# Buck_5V.net
KiCad netlist of a schematic drawn in Altium Designer
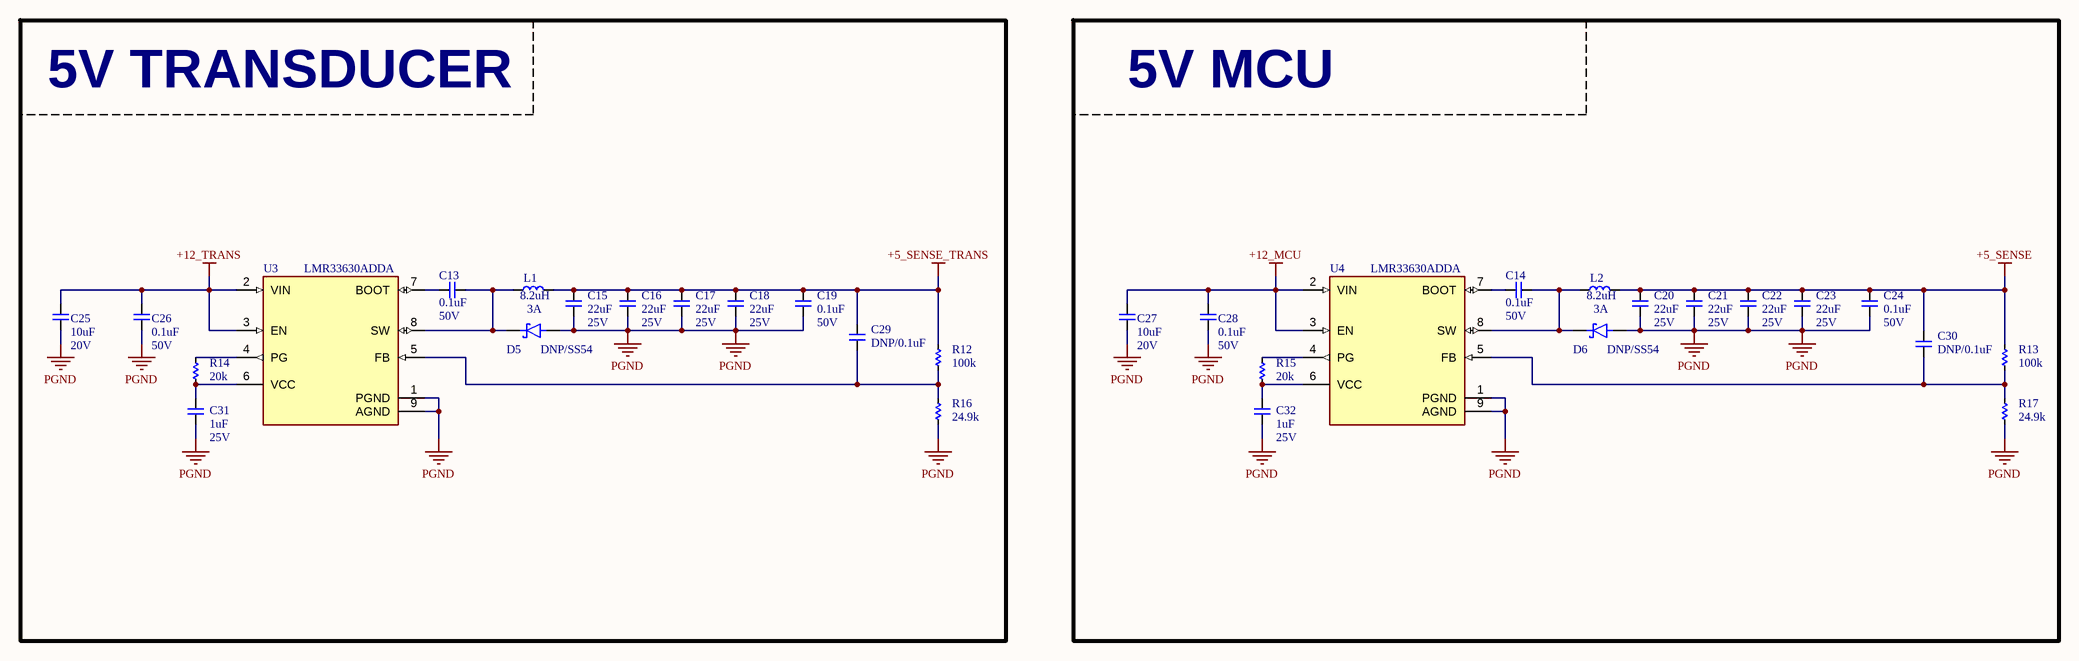
[diagram p0: Buck 5V.SchDoc]

(export (version "E")
  (design (tool "Eeschema 10.0.6"))
  (components
    (comp (ref "C13")
      (value "0.1uF")
      (footprint "CAP_C_1608X80")
      (description "CAP")
      (fields (field (name "VOLTAGE") "50V"))
      (libsource (lib "LABLIB") (part "_CAP_C_2"))
    )
    (comp (ref "C14")
      (value "0.1uF")
      (footprint "CAP_C_1608X80")
      (description "CAP")
      (fields (field (name "VOLTAGE") "50V"))
      (libsource (lib "LABLIB") (part "_CAP_C_2"))
    )
    (comp (ref "C15")
      (value "22uF")
      (footprint "CAP_C_2012X110")
      (description "CAP")
      (fields (field (name "VOLTAGE") "25V"))
      (libsource (lib "LABLIB") (part "_CAP_C_2"))
    )
    (comp (ref "C16")
      (value "22uF")
      (footprint "CAP_C_2012X110")
      (description "CAP")
      (fields (field (name "VOLTAGE") "25V"))
      (libsource (lib "LABLIB") (part "_CAP_C_2"))
    )
    (comp (ref "C17")
      (value "22uF")
      (footprint "CAP_C_2012X110")
      (description "CAP")
      (fields (field (name "VOLTAGE") "25V"))
      (libsource (lib "LABLIB") (part "_CAP_C_2"))
    )
    (comp (ref "C18")
      (value "22uF")
      (footprint "CAP_C_2012X110")
      (description "CAP")
      (fields (field (name "VOLTAGE") "25V"))
      (libsource (lib "LABLIB") (part "_CAP_C_2"))
    )
    (comp (ref "C19")
      (value "0.1uF")
      (footprint "CAP_C_1608X80")
      (description "CAP")
      (fields (field (name "VOLTAGE") "50V"))
      (libsource (lib "LABLIB") (part "_CAP_C_2"))
    )
    (comp (ref "C20")
      (value "22uF")
      (footprint "CAP_C_2012X110")
      (description "CAP")
      (fields (field (name "VOLTAGE") "25V"))
      (libsource (lib "LABLIB") (part "_CAP_C_2"))
    )
    (comp (ref "C21")
      (value "22uF")
      (footprint "CAP_C_2012X110")
      (description "CAP")
      (fields (field (name "VOLTAGE") "25V"))
      (libsource (lib "LABLIB") (part "_CAP_C_2"))
    )
    (comp (ref "C22")
      (value "22uF")
      (footprint "CAP_C_2012X110")
      (description "CAP")
      (fields (field (name "VOLTAGE") "25V"))
      (libsource (lib "LABLIB") (part "_CAP_C_2"))
    )
    (comp (ref "C23")
      (value "22uF")
      (footprint "CAP_C_2012X110")
      (description "CAP")
      (fields (field (name "VOLTAGE") "25V"))
      (libsource (lib "LABLIB") (part "_CAP_C_2"))
    )
    (comp (ref "C24")
      (value "0.1uF")
      (footprint "CAP_C_1608X80")
      (description "CAP")
      (fields (field (name "VOLTAGE") "50V"))
      (libsource (lib "LABLIB") (part "_CAP_C_2"))
    )
    (comp (ref "C25")
      (value "10uF")
      (footprint "CAP_C_2012X110")
      (description "CAP")
      (fields (field (name "VOLTAGE") "20V"))
      (libsource (lib "LABLIB") (part "_CAP_C_2"))
    )
    (comp (ref "C26")
      (value "0.1uF")
      (footprint "CAP_C_1608X80")
      (description "CAP")
      (fields (field (name "VOLTAGE") "50V"))
      (libsource (lib "LABLIB") (part "_CAP_C_2"))
    )
    (comp (ref "C27")
      (value "10uF")
      (footprint "CAP_C_2012X110")
      (description "CAP")
      (fields (field (name "VOLTAGE") "20V"))
      (libsource (lib "LABLIB") (part "_CAP_C_2"))
    )
    (comp (ref "C28")
      (value "0.1uF")
      (footprint "CAP_C_1608X80")
      (description "CAP")
      (fields (field (name "VOLTAGE") "50V"))
      (libsource (lib "LABLIB") (part "_CAP_C_2"))
    )
    (comp (ref "C29")
      (value "DNP/100nF")
      (footprint "CAP_C_1608X80")
      (description "CAP")
      (fields (field (name "VOLTAGE") "DNP/0.1uF"))
      (libsource (lib "LABLIB") (part "_CAP_C_2"))
    )
    (comp (ref "C30")
      (value "DNP/100nF")
      (footprint "CAP_C_1608X80")
      (description "CAP")
      (fields (field (name "VOLTAGE") "DNP/0.1uF"))
      (libsource (lib "LABLIB") (part "_CAP_C_2"))
    )
    (comp (ref "C31")
      (value "1uF")
      (footprint "CAP_C_1608X80")
      (description "CAP")
      (fields (field (name "VOLTAGE") "25V"))
      (libsource (lib "LABLIB") (part "_CAP_C_2"))
    )
    (comp (ref "C32")
      (value "1uF")
      (footprint "CAP_C_1608X80")
      (description "CAP")
      (fields (field (name "VOLTAGE") "25V"))
      (libsource (lib "LABLIB") (part "_CAP_C_2"))
    )
    (comp (ref "D5")
      (value "DNP/SS54")
      (footprint "DO-214AC_SMA")
      (description "DIODE SCHOTTKY")
      (libsource (lib "LABLIB") (part "DIODE SCHOTTKY"))
    )
    (comp (ref "D6")
      (value "DNP/SS54")
      (footprint "DO-214AC_SMA")
      (description "DIODE SCHOTTKY")
      (libsource (lib "LABLIB") (part "DIODE SCHOTTKY"))
    )
    (comp (ref "L1")
      (value "8.2uH")
      (footprint "INDUCTOR 6363")
      (description "Inductor")
      (fields (field (name "VOLTAGE") "3A"))
      (libsource (lib "KIENASIY123_LIB") (part "Inductor"))
    )
    (comp (ref "L2")
      (value "8.2uH")
      (footprint "INDUCTOR 6363")
      (description "Inductor")
      (fields (field (name "VOLTAGE") "3A"))
      (libsource (lib "KIENASIY123_LIB") (part "Inductor"))
    )
    (comp (ref "R12")
      (value "100k")
      (footprint "RES_C_1608X60")
      (description "RES")
      (libsource (lib "LABLIB") (part "_RES_B_2_2"))
    )
    (comp (ref "R13")
      (value "100k")
      (footprint "RES_C_1608X60")
      (description "RES")
      (libsource (lib "LABLIB") (part "_RES_B_2_2"))
    )
    (comp (ref "R14")
      (value "20k")
      (footprint "RES_C_1608X60")
      (description "RES")
      (libsource (lib "LABLIB") (part "_RES_B_2_2"))
    )
    (comp (ref "R15")
      (value "20k")
      (footprint "RES_C_1608X60")
      (description "RES")
      (libsource (lib "LABLIB") (part "_RES_B_2_2"))
    )
    (comp (ref "R16")
      (value "24.9k")
      (footprint "RES_C_1608X60")
      (description "RES")
      (libsource (lib "LABLIB") (part "_RES_B_2_2"))
    )
    (comp (ref "R17")
      (value "24.9k")
      (footprint "RES_C_1608X60")
      (description "RES")
      (libsource (lib "LABLIB") (part "_RES_B_2_2"))
    )
    (comp (ref "U3")
      (value "LMR33630ADDA")
      (footprint "HSOIC_8")
      (libsource (lib "new1") (part "LMR33630ADDA"))
    )
    (comp (ref "U4")
      (value "LMR33630ADDA")
      (footprint "HSOIC_8")
      (libsource (lib "new1") (part "LMR33630ADDA"))
    )
  )
  (nets
    (net (code "1") (name "+5_SENSE") (class "Default")
      (node (ref "C20") (pin "1") (pinfunction "1_1") (pintype "passive"))
      (node (ref "C21") (pin "1") (pinfunction "1_1") (pintype "passive"))
      (node (ref "C22") (pin "1") (pinfunction "1_1") (pintype "passive"))
      (node (ref "C23") (pin "1") (pinfunction "1_1") (pintype "passive"))
      (node (ref "C24") (pin "1") (pinfunction "1_1") (pintype "passive"))
      (node (ref "C30") (pin "1") (pinfunction "1_1") (pintype "passive"))
      (node (ref "L2") (pin "2") (pinfunction "2_2") (pintype "passive"))
      (node (ref "R13") (pin "1") (pinfunction "1_1") (pintype "passive"))
    )
    (net (code "2") (name "+5_SENSE_TRANS") (class "Default")
      (node (ref "C15") (pin "1") (pinfunction "1_1") (pintype "passive"))
      (node (ref "C16") (pin "1") (pinfunction "1_1") (pintype "passive"))
      (node (ref "C17") (pin "1") (pinfunction "1_1") (pintype "passive"))
      (node (ref "C18") (pin "1") (pinfunction "1_1") (pintype "passive"))
      (node (ref "C19") (pin "1") (pinfunction "1_1") (pintype "passive"))
      (node (ref "C29") (pin "1") (pinfunction "1_1") (pintype "passive"))
      (node (ref "L1") (pin "2") (pinfunction "2_2") (pintype "passive"))
      (node (ref "R12") (pin "1") (pinfunction "1_1") (pintype "passive"))
    )
    (net (code "3") (name "+12_MCU") (class "Default")
      (node (ref "C27") (pin "1") (pinfunction "1_1") (pintype "passive"))
      (node (ref "C28") (pin "1") (pinfunction "1_1") (pintype "passive"))
      (node (ref "U4") (pin "2") (pinfunction "VIN_2") (pintype "input"))
      (node (ref "U4") (pin "3") (pinfunction "EN_3") (pintype "input"))
    )
    (net (code "4") (name "+12_TRANS") (class "Default")
      (node (ref "C25") (pin "1") (pinfunction "1_1") (pintype "passive"))
      (node (ref "C26") (pin "1") (pinfunction "1_1") (pintype "passive"))
      (node (ref "U3") (pin "2") (pinfunction "VIN_2") (pintype "input"))
      (node (ref "U3") (pin "3") (pinfunction "EN_3") (pintype "input"))
    )
    (net (code "5") (name "Net-(D5-K)") (class "Default")
      (node (ref "C13") (pin "1") (pinfunction "1_1") (pintype "passive"))
      (node (ref "D5") (pin "1") (pinfunction "K_1") (pintype "passive"))
      (node (ref "L1") (pin "1") (pinfunction "1_1") (pintype "passive"))
      (node (ref "U3") (pin "8") (pinfunction "SW_8") (pintype "bidirectional"))
    )
    (net (code "6") (name "Net-(D6-K)") (class "Default")
      (node (ref "C14") (pin "1") (pinfunction "1_1") (pintype "passive"))
      (node (ref "D6") (pin "1") (pinfunction "K_1") (pintype "passive"))
      (node (ref "L2") (pin "1") (pinfunction "1_1") (pintype "passive"))
      (node (ref "U4") (pin "8") (pinfunction "SW_8") (pintype "bidirectional"))
    )
    (net (code "7") (name "Net-(U3-BOOT)") (class "Default")
      (node (ref "C13") (pin "2") (pinfunction "2_2") (pintype "passive"))
      (node (ref "U3") (pin "7") (pinfunction "BOOT_7") (pintype "bidirectional"))
    )
    (net (code "8") (name "Net-(U3-FB)") (class "Default")
      (node (ref "C29") (pin "2") (pinfunction "2_2") (pintype "passive"))
      (node (ref "R12") (pin "2") (pinfunction "2_2") (pintype "passive"))
      (node (ref "R16") (pin "1") (pinfunction "1_1") (pintype "passive"))
      (node (ref "U3") (pin "5") (pinfunction "FB_5") (pintype "input"))
    )
    (net (code "9") (name "Net-(U3-PG)") (class "Default")
      (node (ref "R14") (pin "1") (pinfunction "1_1") (pintype "passive"))
      (node (ref "U3") (pin "4") (pinfunction "PG_4") (pintype "output"))
    )
    (net (code "10") (name "Net-(U3-VCC)") (class "Default")
      (node (ref "C31") (pin "1") (pinfunction "1_1") (pintype "passive"))
      (node (ref "R14") (pin "2") (pinfunction "2_2") (pintype "passive"))
      (node (ref "U3") (pin "6") (pinfunction "VCC_6") (pintype "power_in"))
    )
    (net (code "11") (name "Net-(U4-BOOT)") (class "Default")
      (node (ref "C14") (pin "2") (pinfunction "2_2") (pintype "passive"))
      (node (ref "U4") (pin "7") (pinfunction "BOOT_7") (pintype "bidirectional"))
    )
    (net (code "12") (name "Net-(U4-FB)") (class "Default")
      (node (ref "C30") (pin "2") (pinfunction "2_2") (pintype "passive"))
      (node (ref "R13") (pin "2") (pinfunction "2_2") (pintype "passive"))
      (node (ref "R17") (pin "1") (pinfunction "1_1") (pintype "passive"))
      (node (ref "U4") (pin "5") (pinfunction "FB_5") (pintype "input"))
    )
    (net (code "13") (name "Net-(U4-PG)") (class "Default")
      (node (ref "R15") (pin "1") (pinfunction "1_1") (pintype "passive"))
      (node (ref "U4") (pin "4") (pinfunction "PG_4") (pintype "output"))
    )
    (net (code "14") (name "Net-(U4-VCC)") (class "Default")
      (node (ref "C32") (pin "1") (pinfunction "1_1") (pintype "passive"))
      (node (ref "R15") (pin "2") (pinfunction "2_2") (pintype "passive"))
      (node (ref "U4") (pin "6") (pinfunction "VCC_6") (pintype "power_in"))
    )
    (net (code "15") (name "PGND") (class "Default")
      (node (ref "C15") (pin "2") (pinfunction "2_2") (pintype "passive"))
      (node (ref "C16") (pin "2") (pinfunction "2_2") (pintype "passive"))
      (node (ref "C17") (pin "2") (pinfunction "2_2") (pintype "passive"))
      (node (ref "C18") (pin "2") (pinfunction "2_2") (pintype "passive"))
      (node (ref "C19") (pin "2") (pinfunction "2_2") (pintype "passive"))
      (node (ref "C20") (pin "2") (pinfunction "2_2") (pintype "passive"))
      (node (ref "C21") (pin "2") (pinfunction "2_2") (pintype "passive"))
      (node (ref "C22") (pin "2") (pinfunction "2_2") (pintype "passive"))
      (node (ref "C23") (pin "2") (pinfunction "2_2") (pintype "passive"))
      (node (ref "C24") (pin "2") (pinfunction "2_2") (pintype "passive"))
      (node (ref "C25") (pin "2") (pinfunction "2_2") (pintype "passive"))
      (node (ref "C26") (pin "2") (pinfunction "2_2") (pintype "passive"))
      (node (ref "C27") (pin "2") (pinfunction "2_2") (pintype "passive"))
      (node (ref "C28") (pin "2") (pinfunction "2_2") (pintype "passive"))
      (node (ref "C31") (pin "2") (pinfunction "2_2") (pintype "passive"))
      (node (ref "C32") (pin "2") (pinfunction "2_2") (pintype "passive"))
      (node (ref "D5") (pin "2") (pinfunction "A_2") (pintype "passive"))
      (node (ref "D6") (pin "2") (pinfunction "A_2") (pintype "passive"))
      (node (ref "R16") (pin "2") (pinfunction "2_2") (pintype "passive"))
      (node (ref "R17") (pin "2") (pinfunction "2_2") (pintype "passive"))
      (node (ref "U3") (pin "1") (pinfunction "PGND_1") (pintype "power_in"))
      (node (ref "U3") (pin "9") (pinfunction "AGND_9") (pintype "power_in"))
      (node (ref "U4") (pin "1") (pinfunction "PGND_1") (pintype "power_in"))
      (node (ref "U4") (pin "9") (pinfunction "AGND_9") (pintype "power_in"))
    )
  )
)
